# clk_gen.net
KiCad netlist of a schematic drawn in Altium Designer
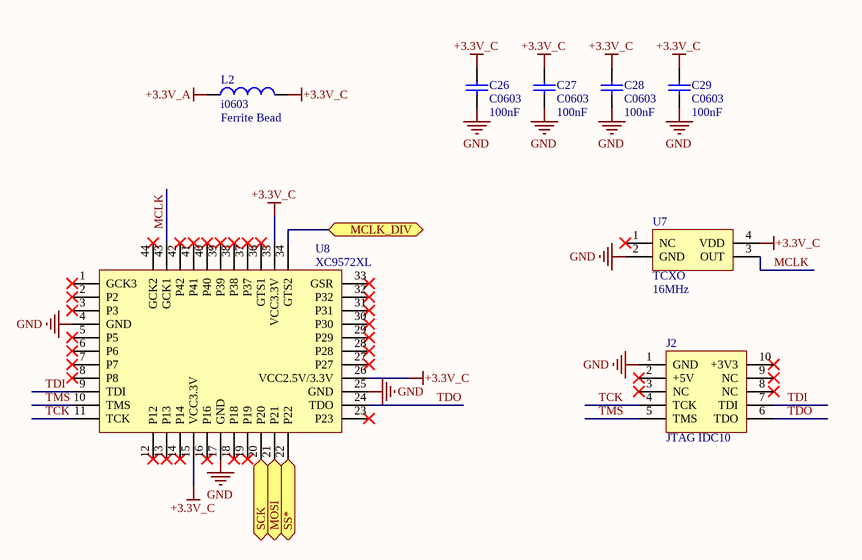
[diagram p0: clk_gen.SchDoc]

(export (version "E")
  (design (tool "Eeschema 10.0.6"))
  (components
    (comp (ref "C26")
      (value "C0603")
      (footprint "0603_HandSoldering")
      (description "Ceramic Capacitor")
      (fields (field (name "ALTIUM_VALUE") "100nF"))
      (libsource (lib "LSP_Schlib") (part "Capacitor"))
    )
    (comp (ref "C27")
      (value "C0603")
      (footprint "0603_HandSoldering")
      (description "Ceramic Capacitor")
      (fields (field (name "ALTIUM_VALUE") "100nF"))
      (libsource (lib "LSP_Schlib") (part "Capacitor"))
    )
    (comp (ref "C28")
      (value "C0603")
      (footprint "0603_HandSoldering")
      (description "Ceramic Capacitor")
      (fields (field (name "ALTIUM_VALUE") "100nF"))
      (libsource (lib "LSP_Schlib") (part "Capacitor"))
    )
    (comp (ref "C29")
      (value "C0603")
      (footprint "0603_HandSoldering")
      (description "Ceramic Capacitor")
      (fields (field (name "ALTIUM_VALUE") "100nF"))
      (libsource (lib "LSP_Schlib") (part "Capacitor"))
    )
    (comp (ref "J2")
      (value "JTAG IDC10")
      (footprint "IDC10")
      (description "JTAG IDC10 Bus Pirate Programming Interface")
      (libsource (lib "LSP_Schlib") (part "JTAG_IDC10"))
    )
    (comp (ref "L2")
      (value "i0603")
      (footprint "0603_HandSoldering")
      (description "Inductor")
      (fields (field (name "ALTIUM_VALUE") "Ferrite Bead"))
      (libsource (lib "LSP_Schlib") (part "Inductor"))
    )
    (comp (ref "U7")
      (value "TCXO")
      (footprint "TCXO_5x3")
      (description "FOX924B-16.000  TCXO, 3.3V CMOS, SMD")
      (fields (field (name "ALTIUM_VALUE") "16MHz"))
      (libsource (lib "LSP_Schlib") (part "TCXO"))
    )
    (comp (ref "U8")
      (value "XC9572XL")
      (footprint "XC9572XL_QFP44")
      (description "Xilinx CPLD 72 Macrocells")
      (libsource (lib "LSP_Schlib") (part "XC9572XL"))
    )
  )
  (nets
    (net (code "1") (name "+3.3V_A") (class "Default")
      (node (ref "L2") (pin "1") (pinfunction "1_1") (pintype "passive"))
    )
    (net (code "2") (name "+3.3V_C") (class "Default")
      (node (ref "C26") (pin "1") (pinfunction "1_1") (pintype "passive"))
      (node (ref "C27") (pin "1") (pinfunction "1_1") (pintype "passive"))
      (node (ref "C28") (pin "1") (pinfunction "1_1") (pintype "passive"))
      (node (ref "C29") (pin "1") (pinfunction "1_1") (pintype "passive"))
      (node (ref "L2") (pin "2") (pinfunction "2_2") (pintype "passive"))
      (node (ref "U7") (pin "4") (pinfunction "VDD_4") (pintype "passive"))
      (node (ref "U8") (pin "15") (pinfunction "VCC3.3V_15") (pintype "passive"))
      (node (ref "U8") (pin "26") (pinfunction "VCC2.5V/3.3V_26") (pintype "passive"))
      (node (ref "U8") (pin "35") (pinfunction "VCC3.3V_35") (pintype "passive"))
    )
    (net (code "3") (name "/MCLK") (class "Default")
      (node (ref "U7") (pin "3") (pinfunction "OUT_3") (pintype "passive"))
      (node (ref "U8") (pin "43") (pinfunction "GCK1_43") (pintype "passive"))
    )
    (net (code "4") (name "/MCLK_DIV") (class "Default")
      (node (ref "U8") (pin "34") (pinfunction "GTS2_34") (pintype "passive"))
    )
    (net (code "5") (name "/MOSI") (class "Default")
      (node (ref "U8") (pin "21") (pinfunction "P21_21") (pintype "passive"))
    )
    (net (code "6") (name "/SCK") (class "Default")
      (node (ref "U8") (pin "20") (pinfunction "P20_20") (pintype "passive"))
    )
    (net (code "7") (name "/SS*") (class "Default")
      (node (ref "U8") (pin "22") (pinfunction "P22_22") (pintype "passive"))
    )
    (net (code "8") (name "/TCK") (class "Default")
      (node (ref "J2") (pin "4") (pinfunction "TCK_4") (pintype "passive"))
      (node (ref "U8") (pin "11") (pinfunction "TCK_11") (pintype "passive"))
    )
    (net (code "9") (name "/TDI") (class "Default")
      (node (ref "J2") (pin "7") (pinfunction "TDI_7") (pintype "passive"))
      (node (ref "U8") (pin "9") (pinfunction "TDI_9") (pintype "passive"))
    )
    (net (code "10") (name "/TDO") (class "Default")
      (node (ref "J2") (pin "6") (pinfunction "TDO_6") (pintype "passive"))
      (node (ref "U8") (pin "24") (pinfunction "TDO_24") (pintype "passive"))
    )
    (net (code "11") (name "/TMS") (class "Default")
      (node (ref "J2") (pin "5") (pinfunction "TMS_5") (pintype "passive"))
      (node (ref "U8") (pin "10") (pinfunction "TMS_10") (pintype "passive"))
    )
    (net (code "12") (name "GND") (class "Default")
      (node (ref "C26") (pin "2") (pinfunction "2_2") (pintype "passive"))
      (node (ref "C27") (pin "2") (pinfunction "2_2") (pintype "passive"))
      (node (ref "C28") (pin "2") (pinfunction "2_2") (pintype "passive"))
      (node (ref "C29") (pin "2") (pinfunction "2_2") (pintype "passive"))
      (node (ref "J2") (pin "1") (pinfunction "GND_1") (pintype "passive"))
      (node (ref "U7") (pin "2") (pinfunction "GND_2") (pintype "passive"))
      (node (ref "U8") (pin "17") (pinfunction "GND_17") (pintype "passive"))
      (node (ref "U8") (pin "25") (pinfunction "GND_25") (pintype "passive"))
      (node (ref "U8") (pin "4") (pinfunction "GND_4") (pintype "passive"))
    )
    (net (code "13") (name "unconnected-(J2-+3V3-Pad10)") (class "Default")
      (node (ref "J2") (pin "10") (pinfunction "+3V3_10") (pintype "passive+no_connect"))
    )
    (net (code "14") (name "unconnected-(J2-+5V-Pad2)") (class "Default")
      (node (ref "J2") (pin "2") (pinfunction "+5V_2") (pintype "passive+no_connect"))
    )
    (net (code "15") (name "unconnected-(J2-NC-Pad3)") (class "Default")
      (node (ref "J2") (pin "3") (pinfunction "NC_3") (pintype "passive+no_connect"))
    )
    (net (code "16") (name "unconnected-(J2-NC-Pad8)") (class "Default")
      (node (ref "J2") (pin "8") (pinfunction "NC_8") (pintype "passive+no_connect"))
    )
    (net (code "17") (name "unconnected-(J2-NC-Pad9)") (class "Default")
      (node (ref "J2") (pin "9") (pinfunction "NC_9") (pintype "passive+no_connect"))
    )
    (net (code "18") (name "unconnected-(U7-NC-Pad1)") (class "Default")
      (node (ref "U7") (pin "1") (pinfunction "NC_1") (pintype "passive+no_connect"))
    )
    (net (code "19") (name "unconnected-(U8-GCK2-Pad44)") (class "Default")
      (node (ref "U8") (pin "44") (pinfunction "GCK2_44") (pintype "passive+no_connect"))
    )
    (net (code "20") (name "unconnected-(U8-GCK3-Pad1)") (class "Default")
      (node (ref "U8") (pin "1") (pinfunction "GCK3_1") (pintype "passive+no_connect"))
    )
    (net (code "21") (name "unconnected-(U8-GSR-Pad33)") (class "Default")
      (node (ref "U8") (pin "33") (pinfunction "GSR_33") (pintype "passive+no_connect"))
    )
    (net (code "22") (name "unconnected-(U8-GTS1-Pad36)") (class "Default")
      (node (ref "U8") (pin "36") (pinfunction "GTS1_36") (pintype "passive+no_connect"))
    )
    (net (code "23") (name "unconnected-(U8-P2-Pad2)") (class "Default")
      (node (ref "U8") (pin "2") (pinfunction "P2_2") (pintype "passive+no_connect"))
    )
    (net (code "24") (name "unconnected-(U8-P3-Pad3)") (class "Default")
      (node (ref "U8") (pin "3") (pinfunction "P3_3") (pintype "passive+no_connect"))
    )
    (net (code "25") (name "unconnected-(U8-P5-Pad5)") (class "Default")
      (node (ref "U8") (pin "5") (pinfunction "P5_5") (pintype "passive+no_connect"))
    )
    (net (code "26") (name "unconnected-(U8-P6-Pad6)") (class "Default")
      (node (ref "U8") (pin "6") (pinfunction "P6_6") (pintype "passive+no_connect"))
    )
    (net (code "27") (name "unconnected-(U8-P7-Pad7)") (class "Default")
      (node (ref "U8") (pin "7") (pinfunction "P7_7") (pintype "passive+no_connect"))
    )
    (net (code "28") (name "unconnected-(U8-P8-Pad8)") (class "Default")
      (node (ref "U8") (pin "8") (pinfunction "P8_8") (pintype "passive+no_connect"))
    )
    (net (code "29") (name "unconnected-(U8-P12-Pad12)") (class "Default")
      (node (ref "U8") (pin "12") (pinfunction "P12_12") (pintype "passive+no_connect"))
    )
    (net (code "30") (name "unconnected-(U8-P13-Pad13)") (class "Default")
      (node (ref "U8") (pin "13") (pinfunction "P13_13") (pintype "passive+no_connect"))
    )
    (net (code "31") (name "unconnected-(U8-P14-Pad14)") (class "Default")
      (node (ref "U8") (pin "14") (pinfunction "P14_14") (pintype "passive+no_connect"))
    )
    (net (code "32") (name "unconnected-(U8-P16-Pad16)") (class "Default")
      (node (ref "U8") (pin "16") (pinfunction "P16_16") (pintype "passive+no_connect"))
    )
    (net (code "33") (name "unconnected-(U8-P18-Pad18)") (class "Default")
      (node (ref "U8") (pin "18") (pinfunction "P18_18") (pintype "passive+no_connect"))
    )
    (net (code "34") (name "unconnected-(U8-P19-Pad19)") (class "Default")
      (node (ref "U8") (pin "19") (pinfunction "P19_19") (pintype "passive+no_connect"))
    )
    (net (code "35") (name "unconnected-(U8-P23-Pad23)") (class "Default")
      (node (ref "U8") (pin "23") (pinfunction "P23_23") (pintype "passive+no_connect"))
    )
    (net (code "36") (name "unconnected-(U8-P27-Pad27)") (class "Default")
      (node (ref "U8") (pin "27") (pinfunction "P27_27") (pintype "passive+no_connect"))
    )
    (net (code "37") (name "unconnected-(U8-P28-Pad28)") (class "Default")
      (node (ref "U8") (pin "28") (pinfunction "P28_28") (pintype "passive+no_connect"))
    )
    (net (code "38") (name "unconnected-(U8-P29-Pad29)") (class "Default")
      (node (ref "U8") (pin "29") (pinfunction "P29_29") (pintype "passive+no_connect"))
    )
    (net (code "39") (name "unconnected-(U8-P30-Pad30)") (class "Default")
      (node (ref "U8") (pin "30") (pinfunction "P30_30") (pintype "passive+no_connect"))
    )
    (net (code "40") (name "unconnected-(U8-P31-Pad31)") (class "Default")
      (node (ref "U8") (pin "31") (pinfunction "P31_31") (pintype "passive+no_connect"))
    )
    (net (code "41") (name "unconnected-(U8-P32-Pad32)") (class "Default")
      (node (ref "U8") (pin "32") (pinfunction "P32_32") (pintype "passive+no_connect"))
    )
    (net (code "42") (name "unconnected-(U8-P37-Pad37)") (class "Default")
      (node (ref "U8") (pin "37") (pinfunction "P37_37") (pintype "passive+no_connect"))
    )
    (net (code "43") (name "unconnected-(U8-P38-Pad38)") (class "Default")
      (node (ref "U8") (pin "38") (pinfunction "P38_38") (pintype "passive+no_connect"))
    )
    (net (code "44") (name "unconnected-(U8-P39-Pad39)") (class "Default")
      (node (ref "U8") (pin "39") (pinfunction "P39_39") (pintype "passive+no_connect"))
    )
    (net (code "45") (name "unconnected-(U8-P40-Pad40)") (class "Default")
      (node (ref "U8") (pin "40") (pinfunction "P40_40") (pintype "passive+no_connect"))
    )
    (net (code "46") (name "unconnected-(U8-P41-Pad41)") (class "Default")
      (node (ref "U8") (pin "41") (pinfunction "P41_41") (pintype "passive+no_connect"))
    )
    (net (code "47") (name "unconnected-(U8-P42-Pad42)") (class "Default")
      (node (ref "U8") (pin "42") (pinfunction "P42_42") (pintype "passive+no_connect"))
    )
  )
)
